# universal_level_converter.net
KiCad netlist of a schematic drawn in EAGLE
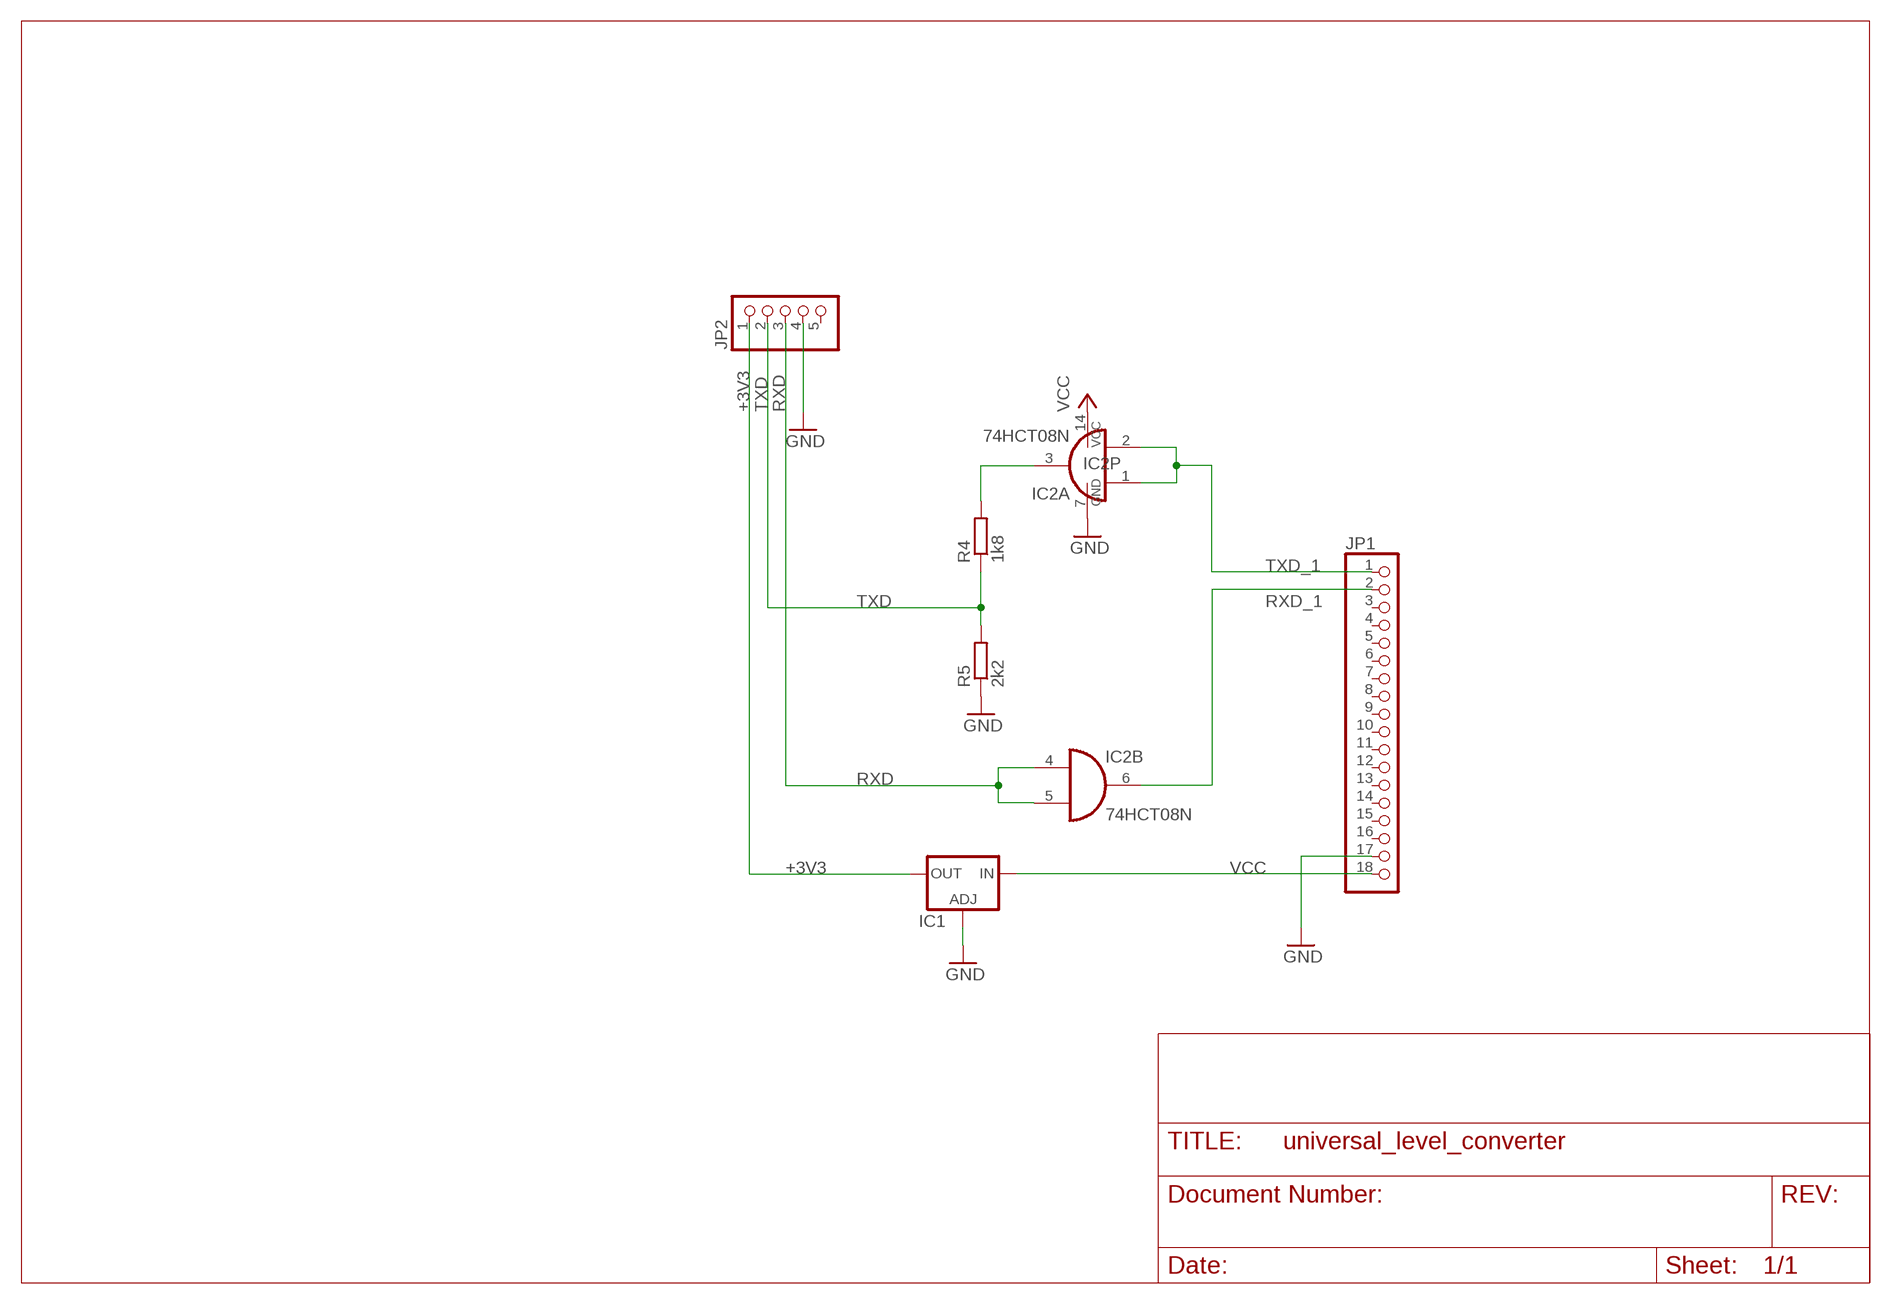
[diagram p0: schematic, sheet 1]

(export (version "E")
  (design (tool "Eeschema 10.0.6"))
  (components
    (comp (ref "IC1")
      (value "LM138-TL")
      (footprint "eagle-import:TO220L1")
      (libsource (lib "eagle-import") (part "LM138-TL"))
    )
    (comp (ref "IC2")
      (value "74HCT08N")
      (footprint "eagle-import:DIL14")
      (libsource (lib "eagle-import") (part "7408NHCT"))
    )
    (comp (ref "JP1")
      (value "PINHD-1X18")
      (footprint "eagle-import:1X18")
      (libsource (lib "eagle-import") (part "PINHD-1X18"))
    )
    (comp (ref "JP2")
      (value "PINHD-1X5")
      (footprint "eagle-import:1X05")
      (libsource (lib "eagle-import") (part "PINHD-1X5"))
    )
    (comp (ref "R4")
      (value "1k8")
      (footprint "eagle-import:0207_10")
      (libsource (lib "eagle-import") (part "R-EU_0207/10"))
    )
    (comp (ref "R5")
      (value "2k2")
      (footprint "eagle-import:0207_10")
      (libsource (lib "eagle-import") (part "R-EU_0207/10"))
    )
  )
  (nets
    (net (code "1") (name "/+3V3") (class "Default")
      (node (ref "IC1") (pin "2") (pinfunction "OUT_2") (pintype "passive"))
      (node (ref "JP2") (pin "1") (pinfunction "1_1") (pintype "passive"))
    )
    (net (code "2") (name "/RXD") (class "Default")
      (node (ref "IC2") (pin "4") (pinfunction "I0_4") (pintype "input"))
      (node (ref "IC2") (pin "5") (pinfunction "I1_5") (pintype "input"))
      (node (ref "JP2") (pin "3") (pinfunction "3_3") (pintype "passive"))
    )
    (net (code "3") (name "/RXD_1") (class "Default")
      (node (ref "IC2") (pin "6") (pinfunction "O_6") (pintype "output"))
      (node (ref "JP1") (pin "2") (pinfunction "2_2") (pintype "passive"))
    )
    (net (code "4") (name "/TXD") (class "Default")
      (node (ref "JP2") (pin "2") (pinfunction "2_2") (pintype "passive"))
      (node (ref "R4") (pin "1") (pinfunction "1_1") (pintype "passive"))
      (node (ref "R5") (pin "2") (pinfunction "2_2") (pintype "passive"))
    )
    (net (code "5") (name "/TXD_1") (class "Default")
      (node (ref "IC2") (pin "1") (pinfunction "I0_1") (pintype "input"))
      (node (ref "IC2") (pin "2") (pinfunction "I1_2") (pintype "input"))
      (node (ref "JP1") (pin "1") (pinfunction "1_1") (pintype "passive"))
    )
    (net (code "6") (name "GND") (class "Default")
      (node (ref "IC1") (pin "1") (pinfunction "ADJ_1") (pintype "input"))
      (node (ref "IC2") (pin "7") (pinfunction "GND_7") (pintype "power_in"))
      (node (ref "JP1") (pin "17") (pinfunction "17_17") (pintype "passive"))
      (node (ref "JP2") (pin "4") (pinfunction "4_4") (pintype "passive"))
      (node (ref "R5") (pin "1") (pinfunction "1_1") (pintype "passive"))
    )
    (net (code "7") (name "Net-(IC2A-O)") (class "Default")
      (node (ref "IC2") (pin "3") (pinfunction "O_3") (pintype "output"))
      (node (ref "R4") (pin "2") (pinfunction "2_2") (pintype "passive"))
    )
    (net (code "8") (name "VCC") (class "Default")
      (node (ref "IC1") (pin "3") (pinfunction "IN_3") (pintype "input"))
      (node (ref "IC2") (pin "14") (pinfunction "VCC_14") (pintype "power_in"))
      (node (ref "JP1") (pin "18") (pinfunction "18_18") (pintype "passive"))
    )
    (net (code "9") (name "unconnected-(JP1-Pad3)") (class "Default")
      (node (ref "JP1") (pin "3") (pinfunction "3_3") (pintype "passive"))
    )
    (net (code "10") (name "unconnected-(JP1-Pad4)") (class "Default")
      (node (ref "JP1") (pin "4") (pinfunction "4_4") (pintype "passive"))
    )
    (net (code "11") (name "unconnected-(JP1-Pad5)") (class "Default")
      (node (ref "JP1") (pin "5") (pinfunction "5_5") (pintype "passive"))
    )
    (net (code "12") (name "unconnected-(JP1-Pad6)") (class "Default")
      (node (ref "JP1") (pin "6") (pinfunction "6_6") (pintype "passive"))
    )
    (net (code "13") (name "unconnected-(JP1-Pad7)") (class "Default")
      (node (ref "JP1") (pin "7") (pinfunction "7_7") (pintype "passive"))
    )
    (net (code "14") (name "unconnected-(JP1-Pad8)") (class "Default")
      (node (ref "JP1") (pin "8") (pinfunction "8_8") (pintype "passive"))
    )
    (net (code "15") (name "unconnected-(JP1-Pad9)") (class "Default")
      (node (ref "JP1") (pin "9") (pinfunction "9_9") (pintype "passive"))
    )
    (net (code "16") (name "unconnected-(JP1-Pad10)") (class "Default")
      (node (ref "JP1") (pin "10") (pinfunction "10_10") (pintype "passive"))
    )
    (net (code "17") (name "unconnected-(JP1-Pad11)") (class "Default")
      (node (ref "JP1") (pin "11") (pinfunction "11_11") (pintype "passive"))
    )
    (net (code "18") (name "unconnected-(JP1-Pad12)") (class "Default")
      (node (ref "JP1") (pin "12") (pinfunction "12_12") (pintype "passive"))
    )
    (net (code "19") (name "unconnected-(JP1-Pad13)") (class "Default")
      (node (ref "JP1") (pin "13") (pinfunction "13_13") (pintype "passive"))
    )
    (net (code "20") (name "unconnected-(JP1-Pad14)") (class "Default")
      (node (ref "JP1") (pin "14") (pinfunction "14_14") (pintype "passive"))
    )
    (net (code "21") (name "unconnected-(JP1-Pad15)") (class "Default")
      (node (ref "JP1") (pin "15") (pinfunction "15_15") (pintype "passive"))
    )
    (net (code "22") (name "unconnected-(JP1-Pad16)") (class "Default")
      (node (ref "JP1") (pin "16") (pinfunction "16_16") (pintype "passive"))
    )
    (net (code "23") (name "unconnected-(JP2-Pad5)") (class "Default")
      (node (ref "JP2") (pin "5") (pinfunction "5_5") (pintype "passive"))
    )
  )
)
